# DGUS.net
KiCad netlist of a schematic drawn in Altium Designer
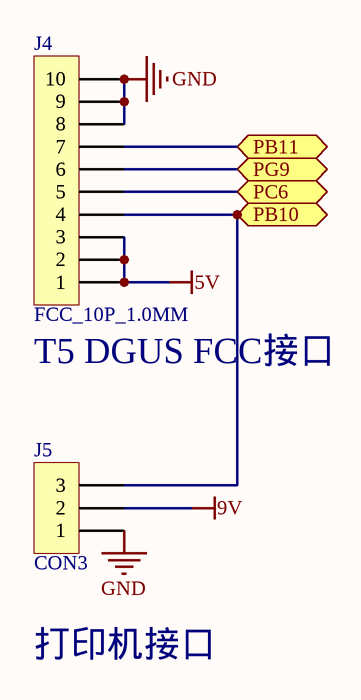
[diagram p0: DGUS&串口打印机.SchDoc]

(export (version "E")
  (design (tool "Eeschema 10.0.6"))
  (components
    (comp (ref "J4")
      (value "FCC_10P_1.0MM")
      (footprint "EXPLORER:FCC_10P")
      (description "连接器")
      (libsource (lib "Connector") (part "CON10"))
    )
    (comp (ref "J5")
      (value "CON3")
      (footprint "Connector:XH2.54-3P")
      (description "连接器")
      (libsource (lib "Connector") (part "CON3"))
    )
  )
  (nets
    (net (code "1") (name "/PB10") (class "Default")
      (node (ref "J4") (pin "4") (pinfunction "4_4") (pintype "passive"))
      (node (ref "J5") (pin "3") (pinfunction "3_3") (pintype "passive"))
    )
    (net (code "2") (name "/PB11") (class "Default")
      (node (ref "J4") (pin "7") (pinfunction "7_7") (pintype "passive"))
    )
    (net (code "3") (name "/PC6") (class "Default")
      (node (ref "J4") (pin "5") (pinfunction "5_5") (pintype "passive"))
    )
    (net (code "4") (name "/PG9") (class "Default")
      (node (ref "J4") (pin "6") (pinfunction "6_6") (pintype "passive"))
    )
    (net (code "5") (name "5V") (class "Default")
      (node (ref "J4") (pin "1") (pinfunction "1_1") (pintype "passive"))
      (node (ref "J4") (pin "2") (pinfunction "2_2") (pintype "passive"))
      (node (ref "J4") (pin "3") (pinfunction "3_3") (pintype "passive"))
    )
    (net (code "6") (name "9V") (class "Default")
      (node (ref "J5") (pin "2") (pinfunction "2_2") (pintype "passive"))
    )
    (net (code "7") (name "GND") (class "Default")
      (node (ref "J4") (pin "10") (pinfunction "10_10") (pintype "passive"))
      (node (ref "J4") (pin "8") (pinfunction "8_8") (pintype "passive"))
      (node (ref "J4") (pin "9") (pinfunction "9_9") (pintype "passive"))
      (node (ref "J5") (pin "1") (pinfunction "1_1") (pintype "passive"))
    )
  )
)
